# User_Interface.net
KiCad netlist of a schematic drawn in Altium Designer
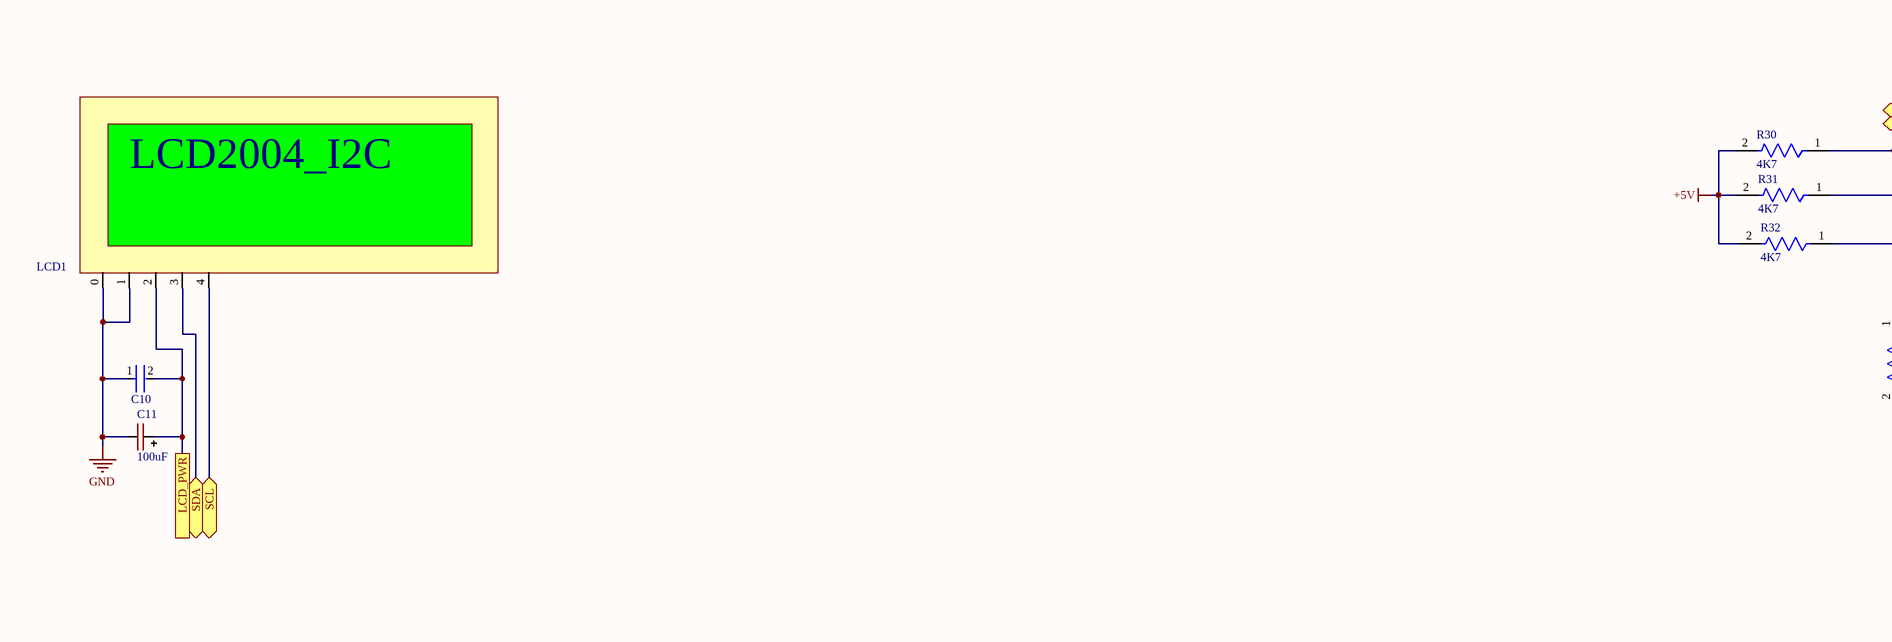
[diagram p0: User_Interface.SchDoc, top left]
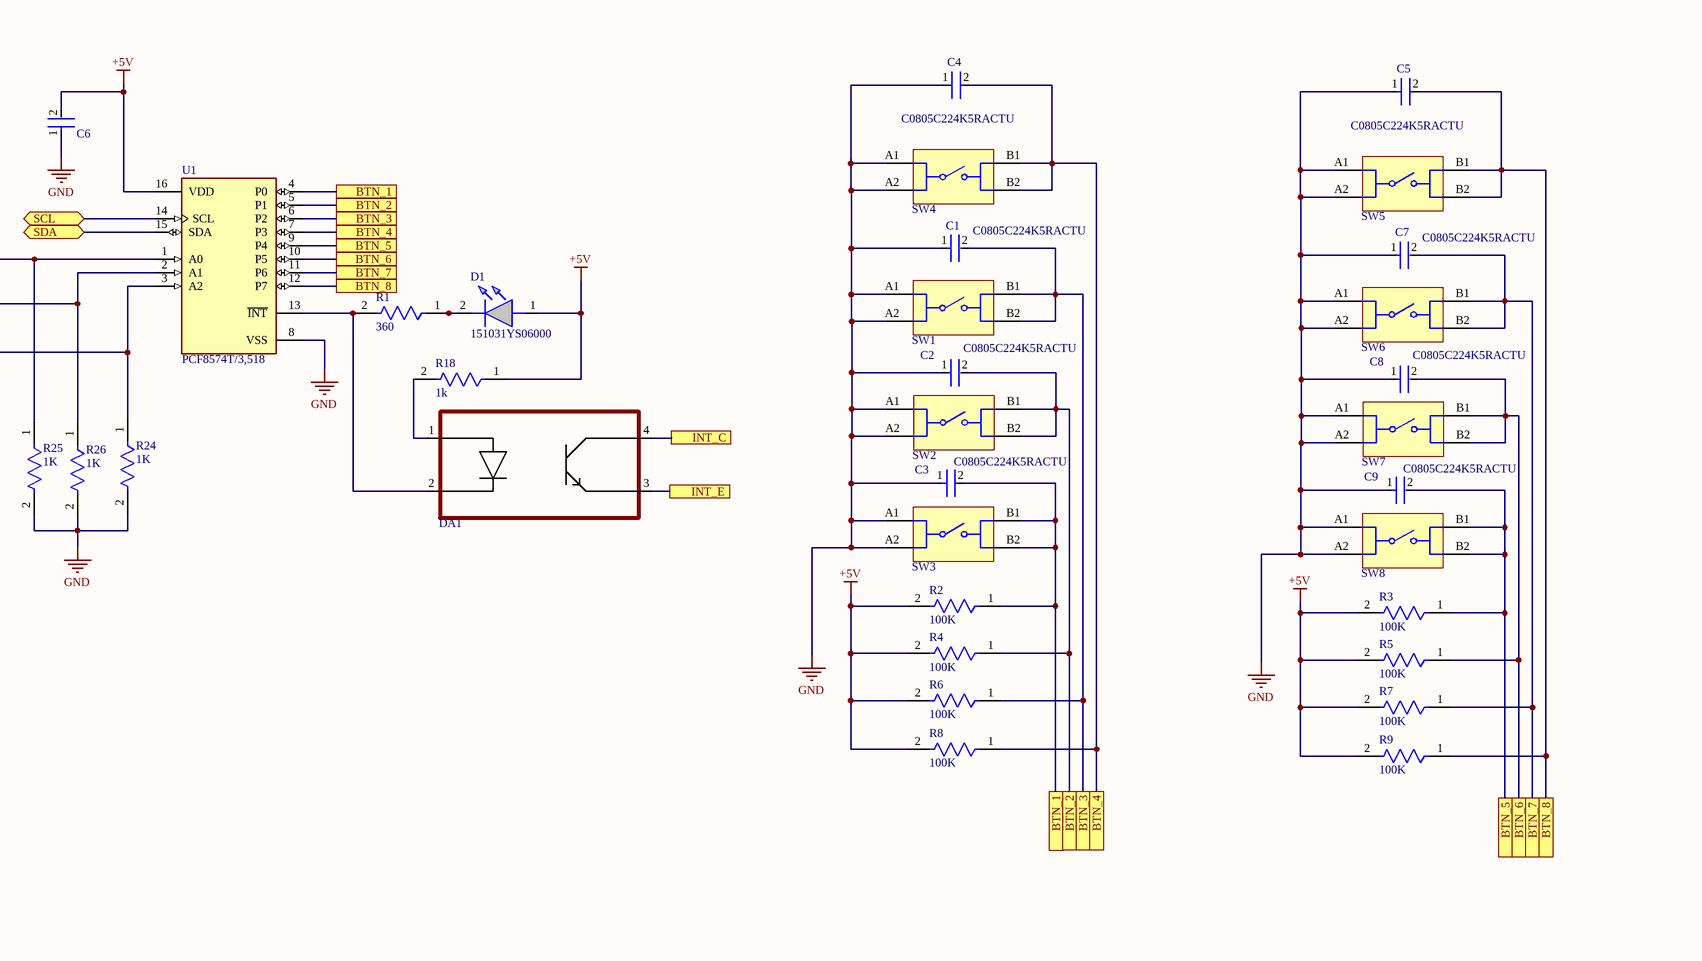
[diagram p1: User_Interface.SchDoc, top right]
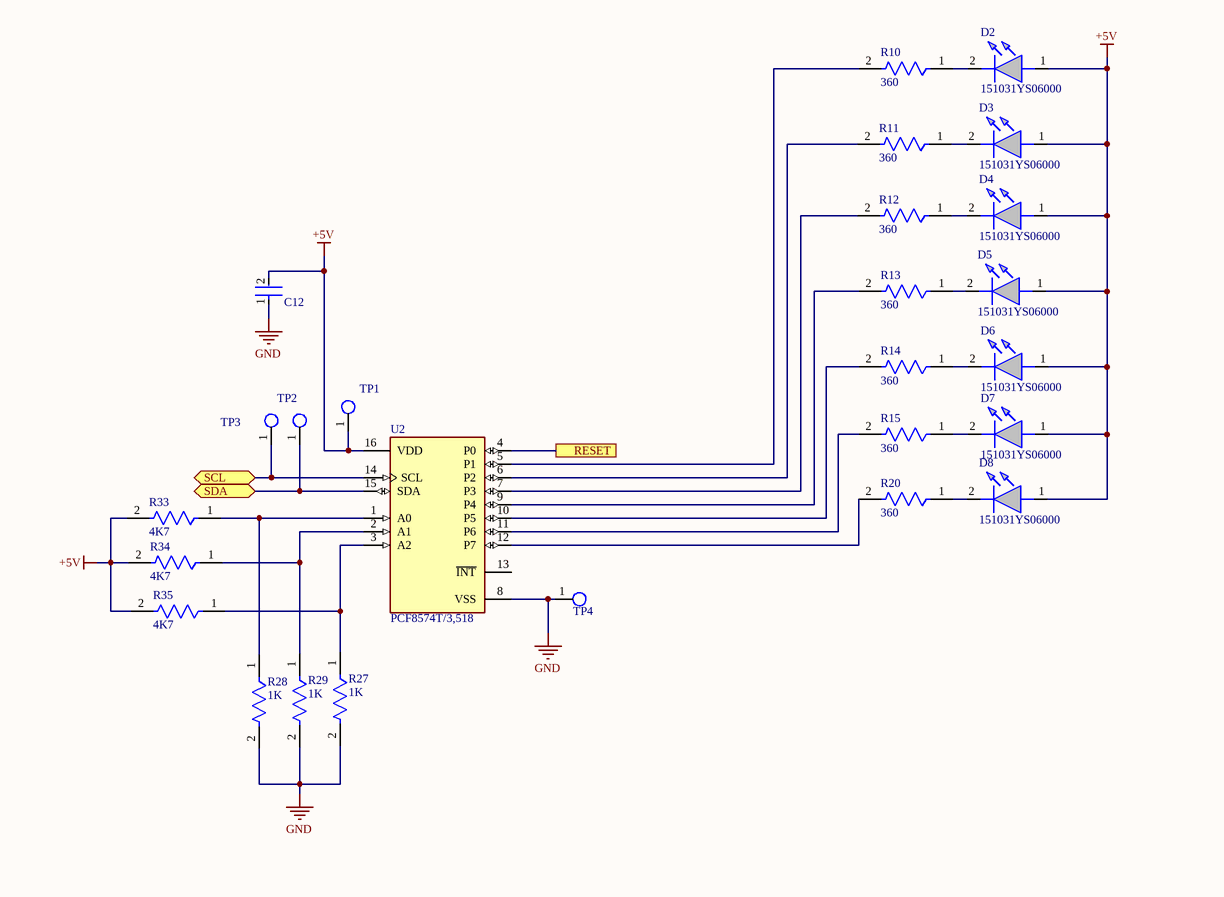
[diagram p2: User_Interface.SchDoc, bottom left]
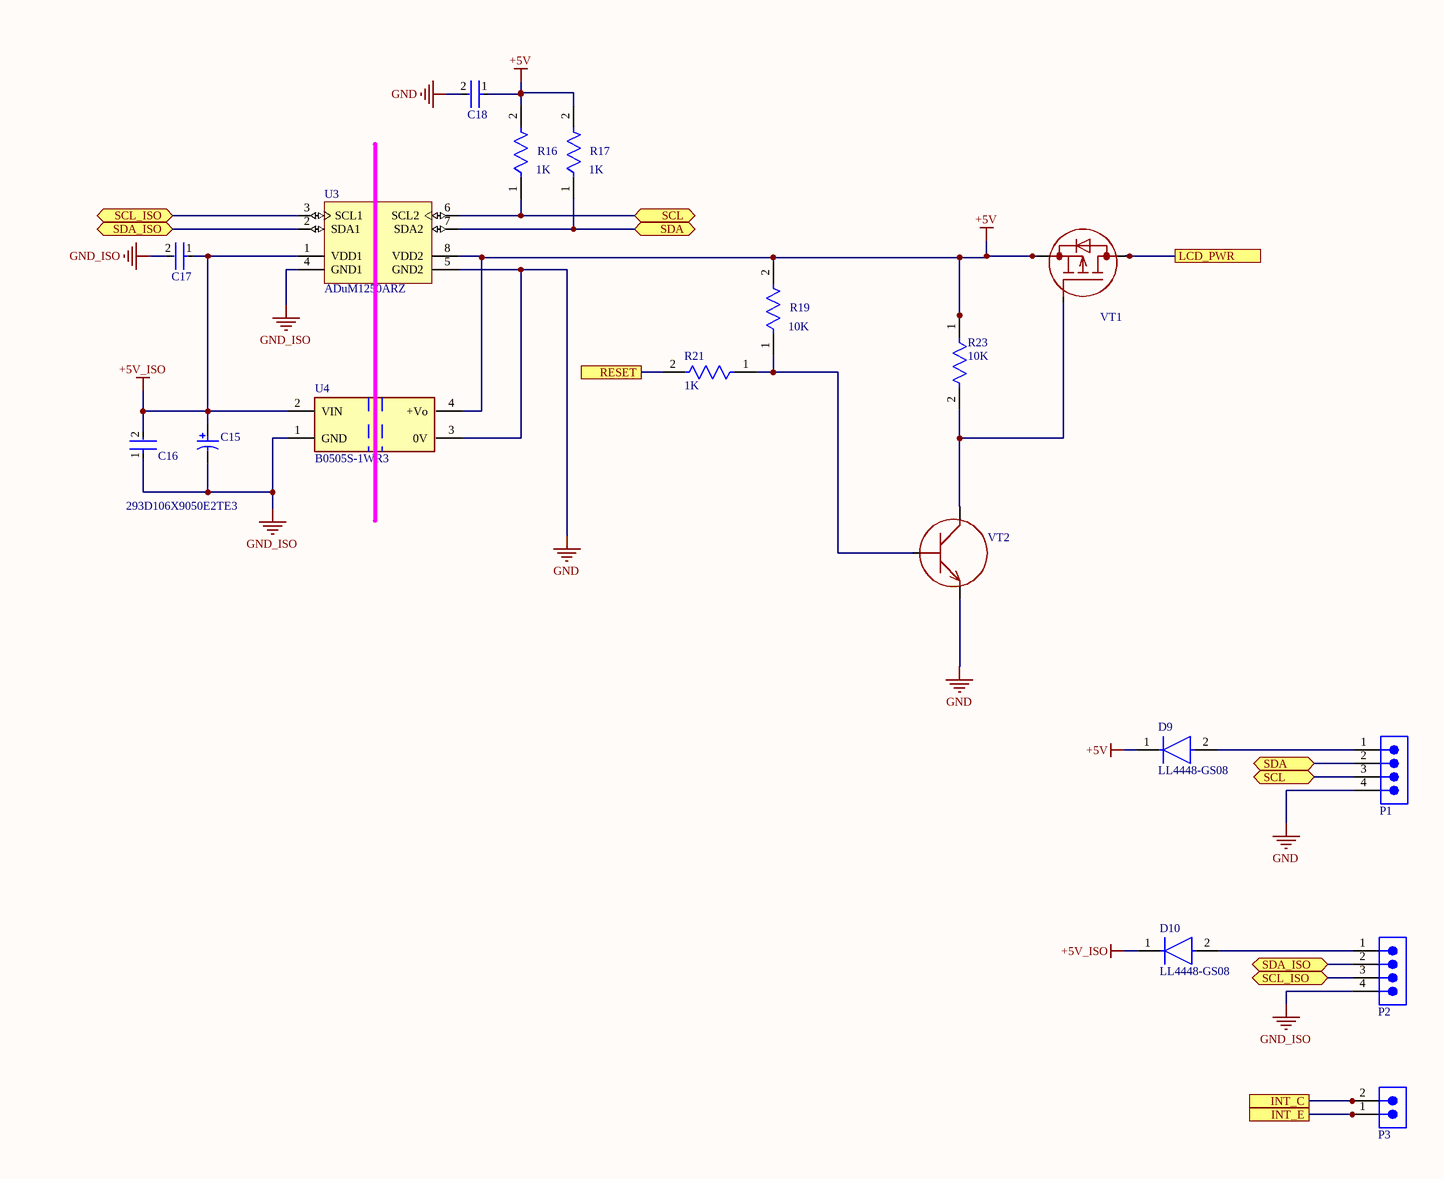
[diagram p3: User_Interface.SchDoc, bottom right]

(export (version "E")
  (design (tool "Eeschema 10.0.6"))
  (components
    (comp (ref "C1")
      (value "C0805C224K5RACTU")
      (footprint "FP-C0805C-DN-IPC_A")
      (description "CAP CER 0.22UF 50V X7R 0805")
      (fields
        (field (name "MANUFACTURER") "KEMET")
        (field (name "OCTOPART") "https://octopart.com/c0805c224k5ractu-kemet-144670")
      )
      (libsource (lib "Pasive_components") (part "CMP-1036-04552-2"))
    )
    (comp (ref "C2")
      (value "C0805C224K5RACTU")
      (footprint "FP-C0805C-DN-IPC_A")
      (description "CAP CER 0.22UF 50V X7R 0805")
      (fields
        (field (name "MANUFACTURER") "KEMET")
        (field (name "OCTOPART") "https://octopart.com/c0805c224k5ractu-kemet-144670")
      )
      (libsource (lib "Pasive_components") (part "CMP-1036-04552-2"))
    )
    (comp (ref "C3")
      (value "C0805C224K5RACTU")
      (footprint "FP-C0805C-DN-IPC_A")
      (description "CAP CER 0.22UF 50V X7R 0805")
      (fields
        (field (name "MANUFACTURER") "KEMET")
        (field (name "OCTOPART") "https://octopart.com/c0805c224k5ractu-kemet-144670")
      )
      (libsource (lib "Pasive_components") (part "CMP-1036-04552-2"))
    )
    (comp (ref "C4")
      (value "C0805C224K5RACTU")
      (footprint "FP-C0805C-DN-IPC_A")
      (description "CAP CER 0.22UF 50V X7R 0805")
      (fields
        (field (name "MANUFACTURER") "KEMET")
        (field (name "OCTOPART") "https://octopart.com/c0805c224k5ractu-kemet-144670")
      )
      (libsource (lib "Pasive_components") (part "CMP-1036-04552-2"))
    )
    (comp (ref "C5")
      (value "C0805C224K5RACTU")
      (footprint "FP-C0805C-DN-IPC_A")
      (description "CAP CER 0.22UF 50V X7R 0805")
      (fields
        (field (name "MANUFACTURER") "KEMET")
        (field (name "OCTOPART") "https://octopart.com/c0805c224k5ractu-kemet-144670")
      )
      (libsource (lib "Pasive_components") (part "CMP-1036-04552-2"))
    )
    (comp (ref "C6")
      (value "C0805C224K5RACTU")
      (footprint "FP-C0805C-DN-IPC_A")
      (description "CAP CER 0.22UF 50V X7R 0805")
      (fields
        (field (name "MANUFACTURER") "KEMET")
        (field (name "OCTOPART") "https://octopart.com/c0805c224k5ractu-kemet-144670")
      )
      (libsource (lib "Pasive_components") (part "CMP-1036-04552-2"))
    )
    (comp (ref "C7")
      (value "C0805C224K5RACTU")
      (footprint "FP-C0805C-DN-IPC_A")
      (description "CAP CER 0.22UF 50V X7R 0805")
      (fields
        (field (name "MANUFACTURER") "KEMET")
        (field (name "OCTOPART") "https://octopart.com/c0805c224k5ractu-kemet-144670")
      )
      (libsource (lib "Pasive_components") (part "CMP-1036-04552-2"))
    )
    (comp (ref "C8")
      (value "C0805C224K5RACTU")
      (footprint "FP-C0805C-DN-IPC_A")
      (description "CAP CER 0.22UF 50V X7R 0805")
      (fields
        (field (name "MANUFACTURER") "KEMET")
        (field (name "OCTOPART") "https://octopart.com/c0805c224k5ractu-kemet-144670")
      )
      (libsource (lib "Pasive_components") (part "CMP-1036-04552-2"))
    )
    (comp (ref "C9")
      (value "C0805C224K5RACTU")
      (footprint "FP-C0805C-DN-IPC_A")
      (description "CAP CER 0.22UF 50V X7R 0805")
      (fields
        (field (name "MANUFACTURER") "KEMET")
        (field (name "OCTOPART") "https://octopart.com/c0805c224k5ractu-kemet-144670")
      )
      (libsource (lib "Pasive_components") (part "CMP-1036-04552-2"))
    )
    (comp (ref "C10")
      (value "C0805C224K5RACTU")
      (footprint "FP-C0805C-DN-IPC_A")
      (description "CAP CER 0.22UF 50V X7R 0805")
      (fields
        (field (name "MANUFACTURER") "KEMET")
        (field (name "OCTOPART") "https://octopart.com/c0805c224k5ractu-kemet-144670")
      )
      (libsource (lib "Pasive_components") (part "CMP-1036-04552-2"))
    )
    (comp (ref "C11")
      (value "100uF")
      (footprint "CAP-TAN-D")
      (libsource (lib "PASSIVE_COMPONENTS") (part "CAP-POLAR"))
    )
    (comp (ref "C12")
      (value "C0805C224K5RACTU")
      (footprint "FP-C0805C-DN-IPC_A")
      (description "CAP CER 0.22UF 50V X7R 0805")
      (fields
        (field (name "MANUFACTURER") "KEMET")
        (field (name "OCTOPART") "https://octopart.com/c0805c224k5ractu-kemet-144670")
      )
      (libsource (lib "Pasive_components") (part "CMP-1036-04552-2"))
    )
    (comp (ref "C15")
      (value "293D106X9050E2TE3")
      (footprint "VISH-293D-E_L")
      (fields (field (name "MANUFACTURER") "Vishay") (field (name "VOLTAGE") "50VDC"))
      (libsource (lib "Altium Content Vault") (part "CAP-P-2"))
    )
    (comp (ref "C16")
      (value "C0805C224K5RACTU")
      (footprint "FP-C0805C-DN-IPC_A")
      (description "CAP CER 0.22UF 50V X7R 0805")
      (fields
        (field (name "MANUFACTURER") "KEMET")
        (field (name "OCTOPART") "https://octopart.com/c0805c224k5ractu-kemet-144670")
      )
      (libsource (lib "Pasive_components") (part "CMP-1036-04552-2"))
    )
    (comp (ref "C17")
      (value "C0805C224K5RACTU")
      (footprint "FP-C0805C-DN-IPC_A")
      (description "CAP CER 0.22UF 50V X7R 0805")
      (fields
        (field (name "MANUFACTURER") "KEMET")
        (field (name "OCTOPART") "https://octopart.com/c0805c224k5ractu-kemet-144670")
      )
      (libsource (lib "Pasive_components") (part "CMP-1036-04552-2"))
    )
    (comp (ref "C18")
      (value "C0805C224K5RACTU")
      (footprint "FP-C0805C-DN-IPC_A")
      (description "CAP CER 0.22UF 50V X7R 0805")
      (fields
        (field (name "MANUFACTURER") "KEMET")
        (field (name "OCTOPART") "https://octopart.com/c0805c224k5ractu-kemet-144670")
      )
      (libsource (lib "Pasive_components") (part "CMP-1036-04552-2"))
    )
    (comp (ref "D1")
      (value "151031YS06000")
      (footprint "LED_BLUE")
      (description "WURTH ELEKTRONIK - 151031YS06000 - LED, Yellow, Through Hole, T-1 (3mm), 30 mA, 2 V, 590 nm")
      (fields (field (name "MOUSER PART NUMBER") "710-151031YS06000"))
      (libsource (lib "Optic-LED") (part "151031YS06000"))
    )
    (comp (ref "D2")
      (value "151031YS06000")
      (footprint "LED_GREEN")
      (description "WURTH ELEKTRONIK - 151031YS06000 - LED, Yellow, Through Hole, T-1 (3mm), 30 mA, 2 V, 590 nm")
      (fields (field (name "MOUSER PART NUMBER") "710-151031YS06000"))
      (libsource (lib "Optic-LED") (part "151031YS06000"))
    )
    (comp (ref "D3")
      (value "151031YS06000")
      (footprint "LED_GREEN")
      (description "WURTH ELEKTRONIK - 151031YS06000 - LED, Yellow, Through Hole, T-1 (3mm), 30 mA, 2 V, 590 nm")
      (fields (field (name "MOUSER PART NUMBER") "710-151031YS06000"))
      (libsource (lib "Optic-LED") (part "151031YS06000"))
    )
    (comp (ref "D4")
      (value "151031YS06000")
      (footprint "LED_GREEN")
      (description "WURTH ELEKTRONIK - 151031YS06000 - LED, Yellow, Through Hole, T-1 (3mm), 30 mA, 2 V, 590 nm")
      (fields (field (name "MOUSER PART NUMBER") "710-151031YS06000"))
      (libsource (lib "Optic-LED") (part "151031YS06000"))
    )
    (comp (ref "D5")
      (value "151031YS06000")
      (footprint "LED_GREEN")
      (description "WURTH ELEKTRONIK - 151031YS06000 - LED, Yellow, Through Hole, T-1 (3mm), 30 mA, 2 V, 590 nm")
      (fields (field (name "MOUSER PART NUMBER") "710-151031YS06000"))
      (libsource (lib "Optic-LED") (part "151031YS06000"))
    )
    (comp (ref "D6")
      (value "151031YS06000")
      (footprint "LED_GREEN")
      (description "WURTH ELEKTRONIK - 151031YS06000 - LED, Yellow, Through Hole, T-1 (3mm), 30 mA, 2 V, 590 nm")
      (fields (field (name "MOUSER PART NUMBER") "710-151031YS06000"))
      (libsource (lib "Optic-LED") (part "151031YS06000"))
    )
    (comp (ref "D7")
      (value "151031YS06000")
      (footprint "LED_GREEN")
      (description "WURTH ELEKTRONIK - 151031YS06000 - LED, Yellow, Through Hole, T-1 (3mm), 30 mA, 2 V, 590 nm")
      (fields (field (name "MOUSER PART NUMBER") "710-151031YS06000"))
      (libsource (lib "Optic-LED") (part "151031YS06000"))
    )
    (comp (ref "D8")
      (value "151031YS06000")
      (footprint "LED_GREEN")
      (description "WURTH ELEKTRONIK - 151031YS06000 - LED, Yellow, Through Hole, T-1 (3mm), 30 mA, 2 V, 590 nm")
      (fields (field (name "MOUSER PART NUMBER") "710-151031YS06000"))
      (libsource (lib "Optic-LED") (part "151031YS06000"))
    )
    (comp (ref "D9")
      (value "LL4448-GS08")
      (footprint "FP-6_560-5005_01-4-MFG")
      (description "DIODE GEN PURP 75V 150MA SOD80")
      (fields
        (field (name "MANUFACTURER") "Vishay Small Signal")
        (field (name "OCTOPART") "https://octopart.com/ll4448-gs08-vishay+small+signal-40886")
      )
      (libsource (lib "Altium Content Vault") (part "d7152d700b627762746794eb795d46e"))
    )
    (comp (ref "D10")
      (value "LL4448-GS08")
      (footprint "FP-6_560-5005_01-4-MFG")
      (description "DIODE GEN PURP 75V 150MA SOD80")
      (fields
        (field (name "MANUFACTURER") "Vishay Small Signal")
        (field (name "OCTOPART") "https://octopart.com/ll4448-gs08-vishay+small+signal-40886")
      )
      (libsource (lib "Altium Content Vault") (part "d7152d700b627762746794eb795d46e"))
    )
    (comp (ref "DA1") (value "PC817") (footprint "4-SMD") (libsource (lib "PC817") (part "PC817")))
    (comp (ref "LCD1")
      (value "2004_I2C")
      (footprint "LCD2004_I2C")
      (libsource (lib "LCD2004") (part "LCD2004_I2C"))
    )
    (comp (ref "P1")
      (value "61900411021")
      (footprint "61900411021")
      (description "WR-WTB THT Male Left Angled Bottom Locking Header, pitch 2.54mm, 4pins")
      (fields (field (name "MANUFACTURER") "Wurth Elektronik"))
      (libsource (lib "Altium_WR-WTB (rev22b)") (part "61900411021"))
    )
    (comp (ref "P2")
      (value "61900411021")
      (footprint "61900411021")
      (description "WR-WTB THT Male Left Angled Bottom Locking Header, pitch 2.54mm, 4pins")
      (fields (field (name "MANUFACTURER") "Wurth Elektronik"))
      (libsource (lib "Altium_WR-WTB (rev22b)") (part "61900411021"))
    )
    (comp (ref "P3")
      (value "61900211021")
      (footprint "61900211021")
      (description "WR-WTB THT Male Left Angled Bottom Locking Header, pitch 2.54mm, 2pins")
      (fields (field (name "MANUFACTURER") "Wurth Elektronik"))
      (libsource (lib "Altium_WR-WTB (rev22b)") (part "61900211021"))
    )
    (comp (ref "R1")
      (value "360")
      (footprint "FP-CRCW0805-e3-MFG")
      (description "RES Thick Film, 200Ω, 1%, 0.125W, 100ppm/°C, 0805")
      (fields (field (name "TOLERANCE") "1%"))
      (libsource (lib "Pasive_components") (part "CMP-2001-04908-2"))
    )
    (comp (ref "R2")
      (value "100K")
      (footprint "FP-CRCW0805-e3-MFG")
      (description "RES Thick Film, 100kΩ, 1%, 0.125W, 100ppm/°C, 0805")
      (fields (field (name "TOLERANCE") "1%"))
      (libsource (lib "Pasive_components") (part "CMP-2001-04908-2"))
    )
    (comp (ref "R3")
      (value "100K")
      (footprint "FP-CRCW0805-e3-MFG")
      (description "RES Thick Film, 100kΩ, 1%, 0.125W, 100ppm/°C, 0805")
      (fields (field (name "TOLERANCE") "1%"))
      (libsource (lib "Pasive_components") (part "CMP-2001-04908-2"))
    )
    (comp (ref "R4")
      (value "100K")
      (footprint "FP-CRCW0805-e3-MFG")
      (description "RES Thick Film, 100kΩ, 1%, 0.125W, 100ppm/°C, 0805")
      (fields (field (name "TOLERANCE") "1%"))
      (libsource (lib "Pasive_components") (part "CMP-2001-04908-2"))
    )
    (comp (ref "R5")
      (value "100K")
      (footprint "FP-CRCW0805-e3-MFG")
      (description "RES Thick Film, 100kΩ, 1%, 0.125W, 100ppm/°C, 0805")
      (fields (field (name "TOLERANCE") "1%"))
      (libsource (lib "Pasive_components") (part "CMP-2001-04908-2"))
    )
    (comp (ref "R6")
      (value "100K")
      (footprint "FP-CRCW0805-e3-MFG")
      (description "RES Thick Film, 100kΩ, 1%, 0.125W, 100ppm/°C, 0805")
      (fields (field (name "TOLERANCE") "1%"))
      (libsource (lib "Pasive_components") (part "CMP-2001-04908-2"))
    )
    (comp (ref "R7")
      (value "100K")
      (footprint "FP-CRCW0805-e3-MFG")
      (description "RES Thick Film, 100kΩ, 1%, 0.125W, 100ppm/°C, 0805")
      (fields (field (name "TOLERANCE") "1%"))
      (libsource (lib "Pasive_components") (part "CMP-2001-04908-2"))
    )
    (comp (ref "R8")
      (value "100K")
      (footprint "FP-CRCW0805-e3-MFG")
      (description "RES Thick Film, 100kΩ, 1%, 0.125W, 100ppm/°C, 0805")
      (fields (field (name "TOLERANCE") "1%"))
      (libsource (lib "Pasive_components") (part "CMP-2001-04908-2"))
    )
    (comp (ref "R9")
      (value "100K")
      (footprint "FP-CRCW0805-e3-MFG")
      (description "RES Thick Film, 100kΩ, 1%, 0.125W, 100ppm/°C, 0805")
      (fields (field (name "TOLERANCE") "1%"))
      (libsource (lib "Pasive_components") (part "CMP-2001-04908-2"))
    )
    (comp (ref "R10")
      (value "360")
      (footprint "FP-CRCW0805-e3-MFG")
      (description "RES Thick Film, 200Ω, 1%, 0.125W, 100ppm/°C, 0805")
      (fields (field (name "TOLERANCE") "1%"))
      (libsource (lib "Pasive_components") (part "CMP-2001-04908-2"))
    )
    (comp (ref "R11")
      (value "360")
      (footprint "FP-CRCW0805-e3-MFG")
      (description "RES Thick Film, 200Ω, 1%, 0.125W, 100ppm/°C, 0805")
      (fields (field (name "TOLERANCE") "1%"))
      (libsource (lib "Pasive_components") (part "CMP-2001-04908-2"))
    )
    (comp (ref "R12")
      (value "360")
      (footprint "FP-CRCW0805-e3-MFG")
      (description "RES Thick Film, 200Ω, 1%, 0.125W, 100ppm/°C, 0805")
      (fields (field (name "TOLERANCE") "1%"))
      (libsource (lib "Pasive_components") (part "CMP-2001-04908-2"))
    )
    (comp (ref "R13")
      (value "360")
      (footprint "FP-CRCW0805-e3-MFG")
      (description "RES Thick Film, 200Ω, 1%, 0.125W, 100ppm/°C, 0805")
      (fields (field (name "TOLERANCE") "1%"))
      (libsource (lib "Pasive_components") (part "CMP-2001-04908-2"))
    )
    (comp (ref "R14")
      (value "360")
      (footprint "FP-CRCW0805-e3-MFG")
      (description "RES Thick Film, 200Ω, 1%, 0.125W, 100ppm/°C, 0805")
      (fields (field (name "TOLERANCE") "1%"))
      (libsource (lib "Pasive_components") (part "CMP-2001-04908-2"))
    )
    (comp (ref "R15")
      (value "360")
      (footprint "FP-CRCW0805-e3-MFG")
      (description "RES Thick Film, 200Ω, 1%, 0.125W, 100ppm/°C, 0805")
      (fields (field (name "TOLERANCE") "1%"))
      (libsource (lib "Pasive_components") (part "CMP-2001-04908-2"))
    )
    (comp (ref "R16")
      (value "1K")
      (footprint "Vishay_CRCW0805-e3_IPC_A")
      (libsource (lib "Pasive_components") (part "CRCW08050000Z0EA"))
    )
    (comp (ref "R17")
      (value "1K")
      (footprint "Vishay_CRCW0805-e3_IPC_A")
      (libsource (lib "Pasive_components") (part "CRCW08050000Z0EA"))
    )
    (comp (ref "R18")
      (value "1k")
      (footprint "FP-CRCW0805-e3-MFG")
      (description "RES Thick Film, 200Ω, 1%, 0.125W, 100ppm/°C, 0805")
      (fields (field (name "TOLERANCE") "1%"))
      (libsource (lib "Pasive_components") (part "CMP-2001-04908-2"))
    )
    (comp (ref "R19")
      (value "10K")
      (footprint "Vishay_CRCW0805-e3_IPC_A")
      (libsource (lib "Pasive_components") (part "CRCW08050000Z0EA"))
    )
    (comp (ref "R20")
      (value "360")
      (footprint "FP-CRCW0805-e3-MFG")
      (description "RES Thick Film, 200Ω, 1%, 0.125W, 100ppm/°C, 0805")
      (fields (field (name "TOLERANCE") "1%"))
      (libsource (lib "Pasive_components") (part "CMP-2001-04908-2"))
    )
    (comp (ref "R21")
      (value "1K")
      (footprint "Vishay_CRCW0805-e3_IPC_A")
      (libsource (lib "Pasive_components") (part "CRCW08050000Z0EA"))
    )
    (comp (ref "R23")
      (value "10K")
      (footprint "Vishay_CRCW0805-e3_IPC_A")
      (libsource (lib "Pasive_components") (part "CRCW08050000Z0EA"))
    )
    (comp (ref "R24")
      (value "1K")
      (footprint "Vishay_CRCW0805-e3_IPC_A")
      (libsource (lib "Pasive_components") (part "CRCW08050000Z0EA"))
    )
    (comp (ref "R25")
      (value "1K")
      (footprint "Vishay_CRCW0805-e3_IPC_A")
      (libsource (lib "Pasive_components") (part "CRCW08050000Z0EA"))
    )
    (comp (ref "R26")
      (value "1K")
      (footprint "Vishay_CRCW0805-e3_IPC_A")
      (libsource (lib "Pasive_components") (part "CRCW08050000Z0EA"))
    )
    (comp (ref "R27")
      (value "1K")
      (footprint "Vishay_CRCW0805-e3_IPC_A")
      (libsource (lib "Pasive_components") (part "CRCW08050000Z0EA"))
    )
    (comp (ref "R28")
      (value "1K")
      (footprint "Vishay_CRCW0805-e3_IPC_A")
      (libsource (lib "Pasive_components") (part "CRCW08050000Z0EA"))
    )
    (comp (ref "R29")
      (value "1K")
      (footprint "Vishay_CRCW0805-e3_IPC_A")
      (libsource (lib "Pasive_components") (part "CRCW08050000Z0EA"))
    )
    (comp (ref "R30")
      (value "4K7")
      (footprint "Vishay_CRCW0805-e3_IPC_A")
      (libsource (lib "Pasive_components") (part "CRCW08050000Z0EA"))
    )
    (comp (ref "R31")
      (value "4K7")
      (footprint "Vishay_CRCW0805-e3_IPC_A")
      (libsource (lib "Pasive_components") (part "CRCW08050000Z0EA"))
    )
    (comp (ref "R32")
      (value "4K7")
      (footprint "Vishay_CRCW0805-e3_IPC_A")
      (libsource (lib "Pasive_components") (part "CRCW08050000Z0EA"))
    )
    (comp (ref "R33")
      (value "4K7")
      (footprint "Vishay_CRCW0805-e3_IPC_A")
      (libsource (lib "Pasive_components") (part "CRCW08050000Z0EA"))
    )
    (comp (ref "R34")
      (value "4K7")
      (footprint "Vishay_CRCW0805-e3_IPC_A")
      (libsource (lib "Pasive_components") (part "CRCW08050000Z0EA"))
    )
    (comp (ref "R35")
      (value "4K7")
      (footprint "Vishay_CRCW0805-e3_IPC_A")
      (libsource (lib "Pasive_components") (part "CRCW08050000Z0EA"))
    )
    (comp (ref "SW1")
      (value "430156043726")
      (footprint "4301x60437x6")
      (description "WS-TATV THT Tact Switch 6x6mm, SPST-NO, 12VDC, 50mA, 260g")
      (fields (field (name "MANUFACTURER") "Wurth Elektronik"))
      (libsource (lib "Altium_WS-TATV (rev22a)") (part "430156043726"))
    )
    (comp (ref "SW2")
      (value "430156043726")
      (footprint "4301x60437x6")
      (description "WS-TATV THT Tact Switch 6x6mm, SPST-NO, 12VDC, 50mA, 260g")
      (fields (field (name "MANUFACTURER") "Wurth Elektronik"))
      (libsource (lib "Altium_WS-TATV (rev22a)") (part "430156043726"))
    )
    (comp (ref "SW3")
      (value "430156043726")
      (footprint "4301x60437x6")
      (description "WS-TATV THT Tact Switch 6x6mm, SPST-NO, 12VDC, 50mA, 260g")
      (fields (field (name "MANUFACTURER") "Wurth Elektronik"))
      (libsource (lib "Altium_WS-TATV (rev22a)") (part "430156043726"))
    )
    (comp (ref "SW4")
      (value "430156043726")
      (footprint "4301x60437x6")
      (description "WS-TATV THT Tact Switch 6x6mm, SPST-NO, 12VDC, 50mA, 260g")
      (fields (field (name "MANUFACTURER") "Wurth Elektronik"))
      (libsource (lib "Altium_WS-TATV (rev22a)") (part "430156043726"))
    )
    (comp (ref "SW5")
      (value "430156043726")
      (footprint "4301x60437x6")
      (description "WS-TATV THT Tact Switch 6x6mm, SPST-NO, 12VDC, 50mA, 260g")
      (fields (field (name "MANUFACTURER") "Wurth Elektronik"))
      (libsource (lib "Altium_WS-TATV (rev22a)") (part "430156043726"))
    )
    (comp (ref "SW6")
      (value "430156043726")
      (footprint "4301x60437x6")
      (description "WS-TATV THT Tact Switch 6x6mm, SPST-NO, 12VDC, 50mA, 260g")
      (fields (field (name "MANUFACTURER") "Wurth Elektronik"))
      (libsource (lib "Altium_WS-TATV (rev22a)") (part "430156043726"))
    )
    (comp (ref "SW7")
      (value "430156043726")
      (footprint "4301x60437x6")
      (description "WS-TATV THT Tact Switch 6x6mm, SPST-NO, 12VDC, 50mA, 260g")
      (fields (field (name "MANUFACTURER") "Wurth Elektronik"))
      (libsource (lib "Altium_WS-TATV (rev22a)") (part "430156043726"))
    )
    (comp (ref "SW8")
      (value "430156043726")
      (footprint "4301x60437x6")
      (description "WS-TATV THT Tact Switch 6x6mm, SPST-NO, 12VDC, 50mA, 260g")
      (fields (field (name "MANUFACTURER") "Wurth Elektronik"))
      (libsource (lib "Altium_WS-TATV (rev22a)") (part "430156043726"))
    )
    (comp (ref "TP1")
      (value "Test_Point_PCB")
      (footprint "Test_Point")
      (description "Test_Point")
      (libsource (lib "Test_Point") (part "TP_PCB?"))
    )
    (comp (ref "TP2")
      (value "Test_Point_PCB")
      (footprint "Test_Point")
      (description "Test_Point")
      (libsource (lib "Test_Point") (part "TP_PCB?"))
    )
    (comp (ref "TP3")
      (value "Test_Point_PCB")
      (footprint "Test_Point")
      (description "Test_Point")
      (libsource (lib "Test_Point") (part "TP_PCB?"))
    )
    (comp (ref "TP4")
      (value "Test_Point_PCB")
      (footprint "Test_Point")
      (description "Test_Point")
      (libsource (lib "Test_Point") (part "TP_PCB?"))
    )
    (comp (ref "U1")
      (value "PCF8574T/3,518")
      (footprint "FP-SOT162-1-MFG")
      (description "IC I/O EXPANDER I2C 8B 16SOIC")
      (fields
        (field (name "MANUFACTURER") "NXP Semiconductors")
        (field (name "OCTOPART") "https://octopart.com/pcf8574t%2F3%2C518-nxp+semiconductors-10470852")
      )
      (libsource (lib "Altium Content Vault") (part "f7fde53ce59de981fb0b266a4e103eb"))
    )
    (comp (ref "U2")
      (value "PCF8574T/3,518")
      (footprint "FP-SOT162-1-MFG")
      (description "IC I/O EXPANDER I2C 8B 16SOIC")
      (fields
        (field (name "MANUFACTURER") "NXP Semiconductors")
        (field (name "OCTOPART") "https://octopart.com/pcf8574t%2F3%2C518-nxp+semiconductors-10470852")
      )
      (libsource (lib "Altium Content Vault") (part "f7fde53ce59de981fb0b266a4e103eb"))
    )
    (comp (ref "U3")
      (value "ADuM1250ARZ")
      (footprint "ADI-R-8_N")
      (description "Hot Swappable, Dual I2C Isolator, 3 to 5.5 V, -40 to 105 degC, 8-Pin SOIC (R-8), RoHS, Tube")
      (fields (field (name "GENERIC PART NUMBER") "ADUM1250"))
      (libsource (lib "ADUM1250-ARZ") (part "CMP-0534-00654-1"))
    )
    (comp (ref "U4")
      (value "B0505S-1WR3")
      (footprint "FP-B0505S-1WR3-MFG")
      (description "DC DC Converter 5V 1W")
      (libsource (lib "B0505S-1W") (part "B0505s-1W"))
    )
    (comp (ref "VT1")
      (value "MOSFET-P-CH")
      (footprint "SOT23-3")
      (libsource (lib "BSS84") (part "MOSFET-P-CH"))
    )
    (comp (ref "VT2") (value "BC847-BEC") (footprint "SOT23-3") (libsource (lib "BC8XX") (part "BC847-BEC")))
  )
  (nets
    (net (code "1") (name "+5V") (class "Default")
      (node (ref "C12") (pin "2") (pinfunction "2_2") (pintype "passive"))
      (node (ref "C18") (pin "1") (pinfunction "1_1") (pintype "passive"))
      (node (ref "C6") (pin "2") (pinfunction "2_2") (pintype "passive"))
      (node (ref "D1") (pin "1") (pinfunction "A_1") (pintype "passive"))
      (node (ref "D2") (pin "1") (pinfunction "A_1") (pintype "passive"))
      (node (ref "D3") (pin "1") (pinfunction "A_1") (pintype "passive"))
      (node (ref "D4") (pin "1") (pinfunction "A_1") (pintype "passive"))
      (node (ref "D5") (pin "1") (pinfunction "A_1") (pintype "passive"))
      (node (ref "D6") (pin "1") (pinfunction "A_1") (pintype "passive"))
      (node (ref "D7") (pin "1") (pinfunction "A_1") (pintype "passive"))
      (node (ref "D8") (pin "1") (pinfunction "A_1") (pintype "passive"))
      (node (ref "D9") (pin "1") (pinfunction "C_1") (pintype "passive"))
      (node (ref "R16") (pin "2") (pinfunction "2_2") (pintype "passive"))
      (node (ref "R17") (pin "2") (pinfunction "2_2") (pintype "passive"))
      (node (ref "R18") (pin "1") (pinfunction "1_1") (pintype "passive"))
      (node (ref "R19") (pin "2") (pinfunction "2_2") (pintype "passive"))
      (node (ref "R2") (pin "2") (pinfunction "2_2") (pintype "passive"))
      (node (ref "R23") (pin "1") (pinfunction "1_1") (pintype "passive"))
      (node (ref "R3") (pin "2") (pinfunction "2_2") (pintype "passive"))
      (node (ref "R30") (pin "2") (pinfunction "2_2") (pintype "passive"))
      (node (ref "R31") (pin "2") (pinfunction "2_2") (pintype "passive"))
      (node (ref "R32") (pin "2") (pinfunction "2_2") (pintype "passive"))
      (node (ref "R33") (pin "2") (pinfunction "2_2") (pintype "passive"))
      (node (ref "R34") (pin "2") (pinfunction "2_2") (pintype "passive"))
      (node (ref "R35") (pin "2") (pinfunction "2_2") (pintype "passive"))
      (node (ref "R4") (pin "2") (pinfunction "2_2") (pintype "passive"))
      (node (ref "R5") (pin "2") (pinfunction "2_2") (pintype "passive"))
      (node (ref "R6") (pin "2") (pinfunction "2_2") (pintype "passive"))
      (node (ref "R7") (pin "2") (pinfunction "2_2") (pintype "passive"))
      (node (ref "R8") (pin "2") (pinfunction "2_2") (pintype "passive"))
      (node (ref "R9") (pin "2") (pinfunction "2_2") (pintype "passive"))
      (node (ref "TP1") (pin "1") (pinfunction "G9_1") (pintype "passive"))
      (node (ref "U1") (pin "16") (pinfunction "VDD_16") (pintype "power_in"))
      (node (ref "U2") (pin "16") (pinfunction "VDD_16") (pintype "power_in"))
      (node (ref "U3") (pin "8") (pinfunction "VDD2_8") (pintype "power_in"))
      (node (ref "U4") (pin "4") (pinfunction "+Vo_4") (pintype "power_in"))
      (node (ref "VT1") (pin "2") (pinfunction "S_2") (pintype "passive"))
    )
    (net (code "2") (name "+5V_ISO") (class "Default")
      (node (ref "C15") (pin "1") (pinfunction "1_1") (pintype "passive"))
      (node (ref "C16") (pin "2") (pinfunction "2_2") (pintype "passive"))
      (node (ref "C17") (pin "1") (pinfunction "1_1") (pintype "passive"))
      (node (ref "D10") (pin "1") (pinfunction "C_1") (pintype "passive"))
      (node (ref "U3") (pin "1") (pinfunction "VDD1_1") (pintype "power_in"))
      (node (ref "U4") (pin "2") (pinfunction "VIN_2") (pintype "power_in"))
    )
    (net (code "3") (name "/BTN_1") (class "Default")
      (node (ref "C3") (pin "2") (pinfunction "2_2") (pintype "passive"))
      (node (ref "R2") (pin "1") (pinfunction "1_1") (pintype "passive"))
      (node (ref "SW3") (pin "B1") (pinfunction "B1_B1") (pintype "passive"))
      (node (ref "SW3") (pin "B2") (pinfunction "B2_B2") (pintype "passive"))
      (node (ref "U1") (pin "4") (pinfunction "P0_4") (pintype "bidirectional"))
    )
    (net (code "4") (name "/BTN_2") (class "Default")
      (node (ref "C2") (pin "2") (pinfunction "2_2") (pintype "passive"))
      (node (ref "R4") (pin "1") (pinfunction "1_1") (pintype "passive"))
      (node (ref "SW2") (pin "B1") (pinfunction "B1_B1") (pintype "passive"))
      (node (ref "SW2") (pin "B2") (pinfunction "B2_B2") (pintype "passive"))
      (node (ref "U1") (pin "5") (pinfunction "P1_5") (pintype "bidirectional"))
    )
    (net (code "5") (name "/BTN_3") (class "Default")
      (node (ref "C1") (pin "2") (pinfunction "2_2") (pintype "passive"))
      (node (ref "R6") (pin "1") (pinfunction "1_1") (pintype "passive"))
      (node (ref "SW1") (pin "B1") (pinfunction "B1_B1") (pintype "passive"))
      (node (ref "SW1") (pin "B2") (pinfunction "B2_B2") (pintype "passive"))
      (node (ref "U1") (pin "6") (pinfunction "P2_6") (pintype "bidirectional"))
    )
    (net (code "6") (name "/BTN_4") (class "Default")
      (node (ref "C4") (pin "2") (pinfunction "2_2") (pintype "passive"))
      (node (ref "R8") (pin "1") (pinfunction "1_1") (pintype "passive"))
      (node (ref "SW4") (pin "B1") (pinfunction "B1_B1") (pintype "passive"))
      (node (ref "SW4") (pin "B2") (pinfunction "B2_B2") (pintype "passive"))
      (node (ref "U1") (pin "7") (pinfunction "P3_7") (pintype "bidirectional"))
    )
    (net (code "7") (name "/BTN_5") (class "Default")
      (node (ref "C9") (pin "2") (pinfunction "2_2") (pintype "passive"))
      (node (ref "R3") (pin "1") (pinfunction "1_1") (pintype "passive"))
      (node (ref "SW8") (pin "B1") (pinfunction "B1_B1") (pintype "passive"))
      (node (ref "SW8") (pin "B2") (pinfunction "B2_B2") (pintype "passive"))
      (node (ref "U1") (pin "9") (pinfunction "P4_9") (pintype "bidirectional"))
    )
    (net (code "8") (name "/BTN_6") (class "Default")
      (node (ref "C8") (pin "2") (pinfunction "2_2") (pintype "passive"))
      (node (ref "R5") (pin "1") (pinfunction "1_1") (pintype "passive"))
      (node (ref "SW7") (pin "B1") (pinfunction "B1_B1") (pintype "passive"))
      (node (ref "SW7") (pin "B2") (pinfunction "B2_B2") (pintype "passive"))
      (node (ref "U1") (pin "10") (pinfunction "P5_10") (pintype "bidirectional"))
    )
    (net (code "9") (name "/BTN_7") (class "Default")
      (node (ref "C7") (pin "2") (pinfunction "2_2") (pintype "passive"))
      (node (ref "R7") (pin "1") (pinfunction "1_1") (pintype "passive"))
      (node (ref "SW6") (pin "B1") (pinfunction "B1_B1") (pintype "passive"))
      (node (ref "SW6") (pin "B2") (pinfunction "B2_B2") (pintype "passive"))
      (node (ref "U1") (pin "11") (pinfunction "P6_11") (pintype "bidirectional"))
    )
    (net (code "10") (name "/BTN_8") (class "Default")
      (node (ref "C5") (pin "2") (pinfunction "2_2") (pintype "passive"))
      (node (ref "R9") (pin "1") (pinfunction "1_1") (pintype "passive"))
      (node (ref "SW5") (pin "B1") (pinfunction "B1_B1") (pintype "passive"))
      (node (ref "SW5") (pin "B2") (pinfunction "B2_B2") (pintype "passive"))
      (node (ref "U1") (pin "12") (pinfunction "P7_12") (pintype "bidirectional"))
    )
    (net (code "11") (name "/INT_C") (class "Default")
      (node (ref "DA1") (pin "4") (pinfunction "COLLECTOR_4") (pintype "passive"))
      (node (ref "P3") (pin "2") (pinfunction "2_2") (pintype "passive"))
    )
    (net (code "12") (name "/INT_E") (class "Default")
      (node (ref "DA1") (pin "3") (pinfunction "EMITTER_3") (pintype "passive"))
      (node (ref "P3") (pin "1") (pinfunction "1_1") (pintype "passive"))
    )
    (net (code "13") (name "/LCD_PWR") (class "Default")
      (node (ref "C10") (pin "2") (pinfunction "2_2") (pintype "passive"))
      (node (ref "C11") (pin "1") (pinfunction "+_1") (pintype "passive"))
      (node (ref "LCD1") (pin "2") (pinfunction "2_2") (pintype "passive"))
      (node (ref "VT1") (pin "3") (pinfunction "D_3") (pintype "passive"))
    )
    (net (code "14") (name "/RESET") (class "Default")
      (node (ref "R21") (pin "2") (pinfunction "2_2") (pintype "passive"))
      (node (ref "U2") (pin "4") (pinfunction "P0_4") (pintype "bidirectional"))
    )
    (net (code "15") (name "/SCL") (class "Default")
      (node (ref "LCD1") (pin "4") (pinfunction "4_4") (pintype "passive"))
      (node (ref "P1") (pin "3") (pinfunction "3_3") (pintype "passive"))
      (node (ref "R16") (pin "1") (pinfunction "1_1") (pintype "passive"))
      (node (ref "TP3") (pin "1") (pinfunction "G9_1") (pintype "passive"))
      (node (ref "U1") (pin "14") (pinfunction "SCL_14") (pintype "input"))
      (node (ref "U2") (pin "14") (pinfunction "SCL_14") (pintype "input"))
      (node (ref "U3") (pin "6") (pinfunction "SCL2_6") (pintype "bidirectional"))
    )
    (net (code "16") (name "/SCL_ISO") (class "Default")
      (node (ref "P2") (pin "3") (pinfunction "3_3") (pintype "passive"))
      (node (ref "U3") (pin "3") (pinfunction "SCL1_3") (pintype "bidirectional"))
    )
    (net (code "17") (name "/SDA") (class "Default")
      (node (ref "LCD1") (pin "3") (pinfunction "3_3") (pintype "passive"))
      (node (ref "P1") (pin "2") (pinfunction "2_2") (pintype "passive"))
      (node (ref "R17") (pin "1") (pinfunction "1_1") (pintype "passive"))
      (node (ref "TP2") (pin "1") (pinfunction "G9_1") (pintype "passive"))
      (node (ref "U1") (pin "15") (pinfunction "SDA_15") (pintype "bidirectional"))
      (node (ref "U2") (pin "15") (pinfunction "SDA_15") (pintype "bidirectional"))
      (node (ref "U3") (pin "7") (pinfunction "SDA2_7") (pintype "bidirectional"))
    )
    (net (code "18") (name "/SDA_ISO") (class "Default")
      (node (ref "P2") (pin "2") (pinfunction "2_2") (pintype "passive"))
      (node (ref "U3") (pin "2") (pinfunction "SDA1_2") (pintype "bidirectional"))
    )
    (net (code "19") (name "GND") (class "Default")
      (node (ref "C1") (pin "1") (pinfunction "1_1") (pintype "passive"))
      (node (ref "C10") (pin "1") (pinfunction "1_1") (pintype "passive"))
      (node (ref "C11") (pin "2") (pinfunction "-_2") (pintype "passive"))
      (node (ref "C12") (pin "1") (pinfunction "1_1") (pintype "passive"))
      (node (ref "C18") (pin "2") (pinfunction "2_2") (pintype "passive"))
      (node (ref "C2") (pin "1") (pinfunction "1_1") (pintype "passive"))
      (node (ref "C3") (pin "1") (pinfunction "1_1") (pintype "passive"))
      (node (ref "C4") (pin "1") (pinfunction "1_1") (pintype "passive"))
      (node (ref "C5") (pin "1") (pinfunction "1_1") (pintype "passive"))
      (node (ref "C6") (pin "1") (pinfunction "1_1") (pintype "passive"))
      (node (ref "C7") (pin "1") (pinfunction "1_1") (pintype "passive"))
      (node (ref "C8") (pin "1") (pinfunction "1_1") (pintype "passive"))
      (node (ref "C9") (pin "1") (pinfunction "1_1") (pintype "passive"))
      (node (ref "LCD1") (pin "0") (pinfunction "0_0") (pintype "passive"))
      (node (ref "LCD1") (pin "1") (pinfunction "1_1") (pintype "passive"))
      (node (ref "P1") (pin "4") (pinfunction "4_4") (pintype "passive"))
      (node (ref "R24") (pin "2") (pinfunction "2_2") (pintype "passive"))
      (node (ref "R25") (pin "2") (pinfunction "2_2") (pintype "passive"))
      (node (ref "R26") (pin "2") (pinfunction "2_2") (pintype "passive"))
      (node (ref "R27") (pin "2") (pinfunction "2_2") (pintype "passive"))
      (node (ref "R28") (pin "2") (pinfunction "2_2") (pintype "passive"))
      (node (ref "R29") (pin "2") (pinfunction "2_2") (pintype "passive"))
      (node (ref "SW1") (pin "A1") (pinfunction "A1_A1") (pintype "passive"))
      (node (ref "SW1") (pin "A2") (pinfunction "A2_A2") (pintype "passive"))
      (node (ref "SW2") (pin "A1") (pinfunction "A1_A1") (pintype "passive"))
      (node (ref "SW2") (pin "A2") (pinfunction "A2_A2") (pintype "passive"))
      (node (ref "SW3") (pin "A1") (pinfunction "A1_A1") (pintype "passive"))
      (node (ref "SW3") (pin "A2") (pinfunction "A2_A2") (pintype "passive"))
      (node (ref "SW4") (pin "A1") (pinfunction "A1_A1") (pintype "passive"))
      (node (ref "SW4") (pin "A2") (pinfunction "A2_A2") (pintype "passive"))
      (node (ref "SW5") (pin "A1") (pinfunction "A1_A1") (pintype "passive"))
      (node (ref "SW5") (pin "A2") (pinfunction "A2_A2") (pintype "passive"))
      (node (ref "SW6") (pin "A1") (pinfunction "A1_A1") (pintype "passive"))
      (node (ref "SW6") (pin "A2") (pinfunction "A2_A2") (pintype "passive"))
      (node (ref "SW7") (pin "A1") (pinfunction "A1_A1") (pintype "passive"))
      (node (ref "SW7") (pin "A2") (pinfunction "A2_A2") (pintype "passive"))
      (node (ref "SW8") (pin "A1") (pinfunction "A1_A1") (pintype "passive"))
      (node (ref "SW8") (pin "A2") (pinfunction "A2_A2") (pintype "passive"))
      (node (ref "TP4") (pin "1") (pinfunction "G9_1") (pintype "passive"))
      (node (ref "U1") (pin "8") (pinfunction "VSS_8") (pintype "power_in"))
      (node (ref "U2") (pin "8") (pinfunction "VSS_8") (pintype "power_in"))
      (node (ref "U3") (pin "5") (pinfunction "GND2_5") (pintype "power_in"))
      (node (ref "U4") (pin "3") (pinfunction "0V_3") (pintype "power_in"))
      (node (ref "VT2") (pin "2") (pinfunction "E_2") (pintype "passive"))
    )
    (net (code "20") (name "GND_ISO") (class "Default")
      (node (ref "C15") (pin "2") (pinfunction "2_2") (pintype "passive"))
      (node (ref "C16") (pin "1") (pinfunction "1_1") (pintype "passive"))
      (node (ref "C17") (pin "2") (pinfunction "2_2") (pintype "passive"))
      (node (ref "P2") (pin "4") (pinfunction "4_4") (pintype "passive"))
      (node (ref "U3") (pin "4") (pinfunction "GND1_4") (pintype "power_in"))
      (node (ref "U4") (pin "1") (pinfunction "GND_1") (pintype "power_in"))
    )
    (net (code "21") (name "Net-(D1-K)") (class "Default")
      (node (ref "D1") (pin "2") (pinfunction "K_2") (pintype "passive"))
      (node (ref "R1") (pin "1") (pinfunction "1_1") (pintype "passive"))
    )
    (net (code "22") (name "Net-(D2-K)") (class "Default")
      (node (ref "D2") (pin "2") (pinfunction "K_2") (pintype "passive"))
      (node (ref "R10") (pin "1") (pinfunction "1_1") (pintype "passive"))
    )
    (net (code "23") (name "Net-(D3-K)") (class "Default")
      (node (ref "D3") (pin "2") (pinfunction "K_2") (pintype "passive"))
      (node (ref "R11") (pin "1") (pinfunction "1_1") (pintype "passive"))
    )
    (net (code "24") (name "Net-(D4-K)") (class "Default")
      (node (ref "D4") (pin "2") (pinfunction "K_2") (pintype "passive"))
      (node (ref "R12") (pin "1") (pinfunction "1_1") (pintype "passive"))
    )
    (net (code "25") (name "Net-(D5-K)") (class "Default")
      (node (ref "D5") (pin "2") (pinfunction "K_2") (pintype "passive"))
      (node (ref "R13") (pin "1") (pinfunction "1_1") (pintype "passive"))
    )
    (net (code "26") (name "Net-(D6-K)") (class "Default")
      (node (ref "D6") (pin "2") (pinfunction "K_2") (pintype "passive"))
      (node (ref "R14") (pin "1") (pinfunction "1_1") (pintype "passive"))
    )
    (net (code "27") (name "Net-(D7-K)") (class "Default")
      (node (ref "D7") (pin "2") (pinfunction "K_2") (pintype "passive"))
      (node (ref "R15") (pin "1") (pinfunction "1_1") (pintype "passive"))
    )
    (net (code "28") (name "Net-(D8-K)") (class "Default")
      (node (ref "D8") (pin "2") (pinfunction "K_2") (pintype "passive"))
      (node (ref "R20") (pin "1") (pinfunction "1_1") (pintype "passive"))
    )
    (net (code "29") (name "Net-(D9-A)") (class "Default")
      (node (ref "D9") (pin "2") (pinfunction "A_2") (pintype "passive"))
      (node (ref "P1") (pin "1") (pinfunction "1_1") (pintype "passive"))
    )
    (net (code "30") (name "Net-(D10-A)") (class "Default")
      (node (ref "D10") (pin "2") (pinfunction "A_2") (pintype "passive"))
      (node (ref "P2") (pin "1") (pinfunction "1_1") (pintype "passive"))
    )
    (net (code "31") (name "Net-(DA1-ANODE)") (class "Default")
      (node (ref "DA1") (pin "1") (pinfunction "ANODE_1") (pintype "passive"))
      (node (ref "R18") (pin "2") (pinfunction "2_2") (pintype "passive"))
    )
    (net (code "32") (name "Net-(DA1-CATHODE)") (class "Default")
      (node (ref "DA1") (pin "2") (pinfunction "CATHODE_2") (pintype "passive"))
      (node (ref "R1") (pin "2") (pinfunction "2_2") (pintype "passive"))
      (node (ref "U1") (pin "13") (pinfunction "~{INT}_13") (pintype "open_collector"))
    )
    (net (code "33") (name "Net-(U1-A0)") (class "Default")
      (node (ref "R25") (pin "1") (pinfunction "1_1") (pintype "passive"))
      (node (ref "R30") (pin "1") (pinfunction "1_1") (pintype "passive"))
      (node (ref "U1") (pin "1") (pinfunction "A0_1") (pintype "input"))
    )
    (net (code "34") (name "Net-(U1-A1)") (class "Default")
      (node (ref "R26") (pin "1") (pinfunction "1_1") (pintype "passive"))
      (node (ref "R31") (pin "1") (pinfunction "1_1") (pintype "passive"))
      (node (ref "U1") (pin "2") (pinfunction "A1_2") (pintype "input"))
    )
    (net (code "35") (name "Net-(U1-A2)") (class "Default")
      (node (ref "R24") (pin "1") (pinfunction "1_1") (pintype "passive"))
      (node (ref "R32") (pin "1") (pinfunction "1_1") (pintype "passive"))
      (node (ref "U1") (pin "3") (pinfunction "A2_3") (pintype "input"))
    )
    (net (code "36") (name "Net-(U2-A0)") (class "Default")
      (node (ref "R28") (pin "1") (pinfunction "1_1") (pintype "passive"))
      (node (ref "R33") (pin "1") (pinfunction "1_1") (pintype "passive"))
      (node (ref "U2") (pin "1") (pinfunction "A0_1") (pintype "input"))
    )
    (net (code "37") (name "Net-(U2-A1)") (class "Default")
      (node (ref "R29") (pin "1") (pinfunction "1_1") (pintype "passive"))
      (node (ref "R34") (pin "1") (pinfunction "1_1") (pintype "passive"))
      (node (ref "U2") (pin "2") (pinfunction "A1_2") (pintype "input"))
    )
    (net (code "38") (name "Net-(U2-A2)") (class "Default")
      (node (ref "R27") (pin "1") (pinfunction "1_1") (pintype "passive"))
      (node (ref "R35") (pin "1") (pinfunction "1_1") (pintype "passive"))
      (node (ref "U2") (pin "3") (pinfunction "A2_3") (pintype "input"))
    )
    (net (code "39") (name "Net-(U2-P1)") (class "Default")
      (node (ref "R10") (pin "2") (pinfunction "2_2") (pintype "passive"))
      (node (ref "U2") (pin "5") (pinfunction "P1_5") (pintype "bidirectional"))
    )
    (net (code "40") (name "Net-(U2-P2)") (class "Default")
      (node (ref "R11") (pin "2") (pinfunction "2_2") (pintype "passive"))
      (node (ref "U2") (pin "6") (pinfunction "P2_6") (pintype "bidirectional"))
    )
    (net (code "41") (name "Net-(U2-P3)") (class "Default")
      (node (ref "R12") (pin "2") (pinfunction "2_2") (pintype "passive"))
      (node (ref "U2") (pin "7") (pinfunction "P3_7") (pintype "bidirectional"))
    )
    (net (code "42") (name "Net-(U2-P4)") (class "Default")
      (node (ref "R13") (pin "2") (pinfunction "2_2") (pintype "passive"))
      (node (ref "U2") (pin "9") (pinfunction "P4_9") (pintype "bidirectional"))
    )
    (net (code "43") (name "Net-(U2-P5)") (class "Default")
      (node (ref "R14") (pin "2") (pinfunction "2_2") (pintype "passive"))
      (node (ref "U2") (pin "10") (pinfunction "P5_10") (pintype "bidirectional"))
    )
    (net (code "44") (name "Net-(U2-P6)") (class "Default")
      (node (ref "R15") (pin "2") (pinfunction "2_2") (pintype "passive"))
      (node (ref "U2") (pin "11") (pinfunction "P6_11") (pintype "bidirectional"))
    )
    (net (code "45") (name "Net-(U2-P7)") (class "Default")
      (node (ref "R20") (pin "2") (pinfunction "2_2") (pintype "passive"))
      (node (ref "U2") (pin "12") (pinfunction "P7_12") (pintype "bidirectional"))
    )
    (net (code "46") (name "Net-(VT1-G)") (class "Default")
      (node (ref "R23") (pin "2") (pinfunction "2_2") (pintype "passive"))
      (node (ref "VT1") (pin "1") (pinfunction "G_1") (pintype "passive"))
      (node (ref "VT2") (pin "3") (pinfunction "C_3") (pintype "passive"))
    )
    (net (code "47") (name "Net-(VT2-B)") (class "Default")
      (node (ref "R19") (pin "1") (pinfunction "1_1") (pintype "passive"))
      (node (ref "R21") (pin "1") (pinfunction "1_1") (pintype "passive"))
      (node (ref "VT2") (pin "1") (pinfunction "B_1") (pintype "passive"))
    )
    (net (code "48") (name "unconnected-(U2-~{INT}-Pad13)") (class "Default")
      (node (ref "U2") (pin "13") (pinfunction "~{INT}_13") (pintype "open_collector"))
    )
  )
)
